# Power_Outlet.net
KiCad netlist of a schematic drawn in EAGLE
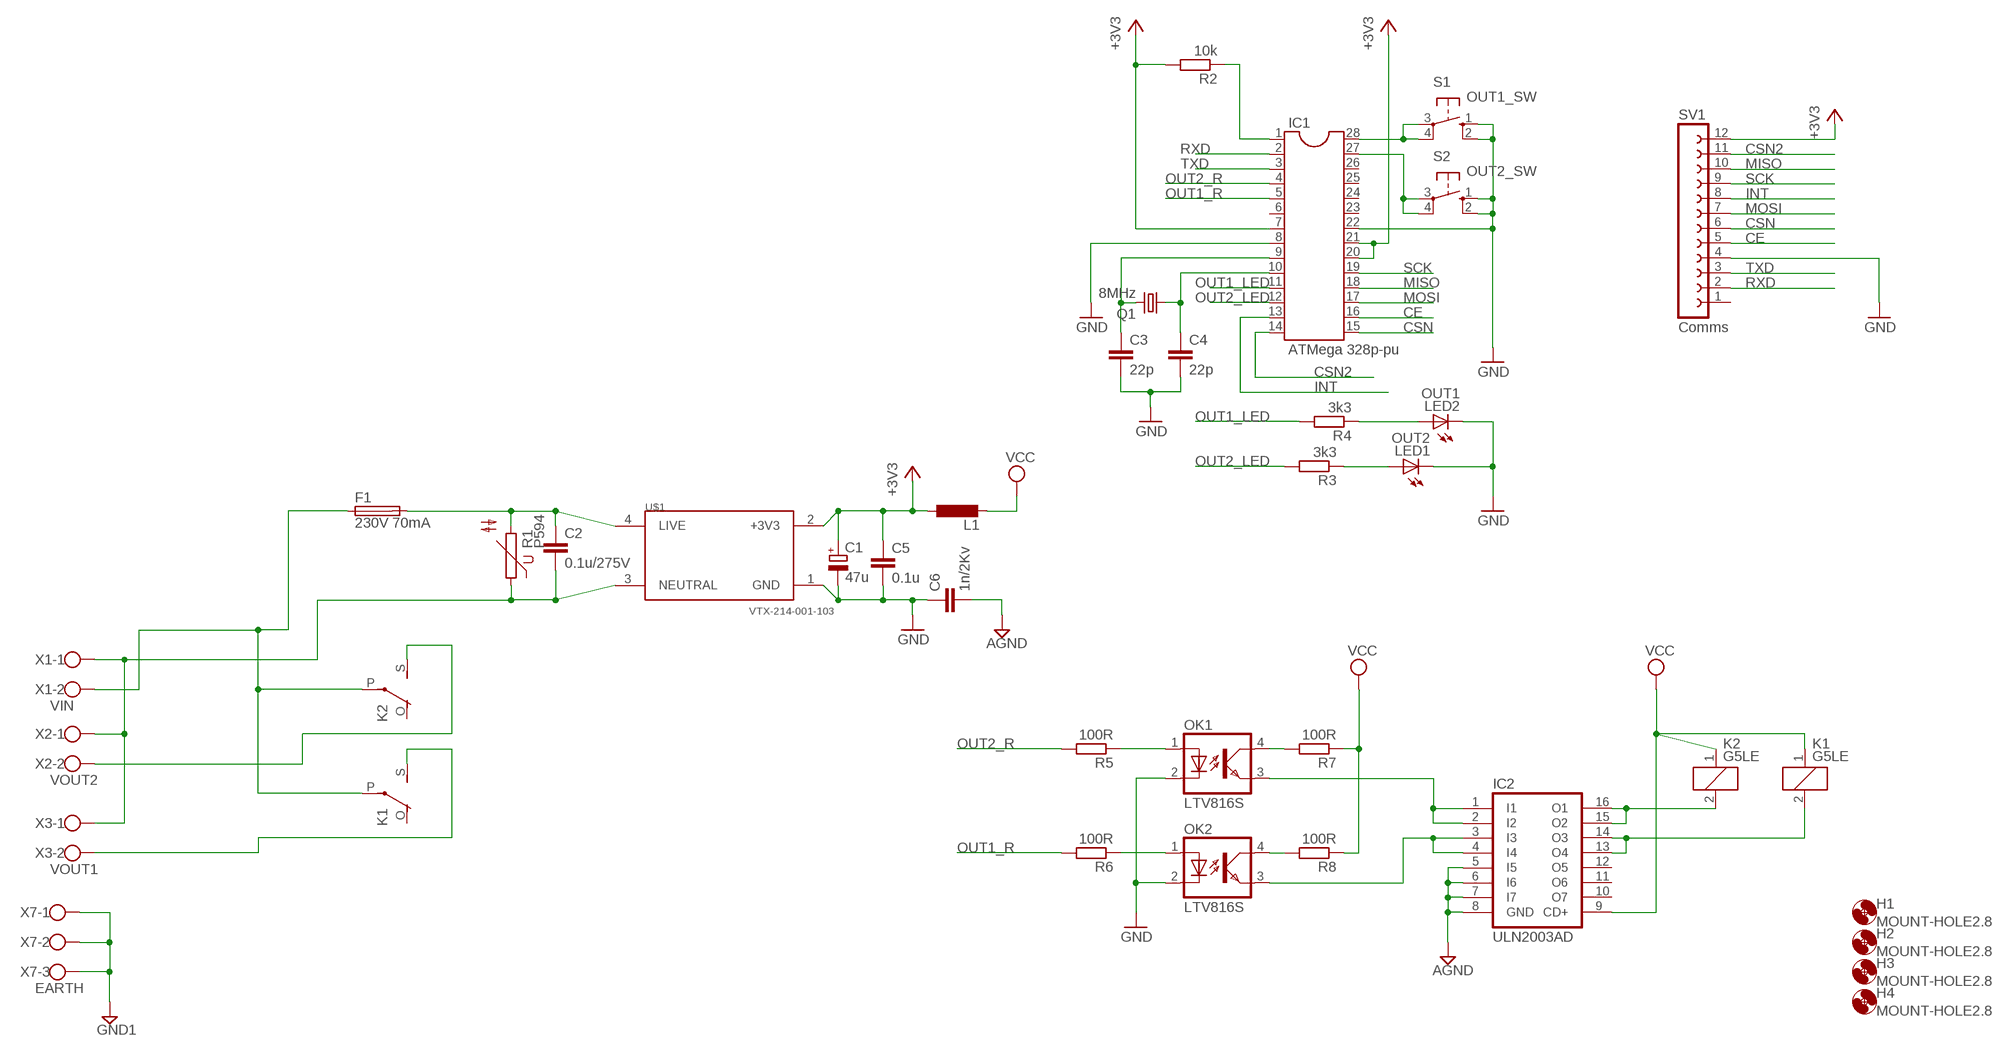
[diagram p0: schematic, sheet 1]

(export (version "E")
  (design (tool "Eeschema 10.0.6"))
  (components
    (comp (ref "C1")
      (value "47u")
      (footprint "eagle-import:E2,5-6E")
      (libsource (lib "eagle-import") (part "CPOL-EUE2,5-6E"))
    )
    (comp (ref "C2")
      (value "0.1u/275V")
      (footprint "eagle-import:C050-030X075")
      (libsource (lib "eagle-import") (part "C-EU050-030X075"))
    )
    (comp (ref "C3")
      (value "22p")
      (footprint "eagle-import:C1206K")
      (libsource (lib "eagle-import") (part "C-EUC1206K"))
    )
    (comp (ref "C4")
      (value "22p")
      (footprint "eagle-import:C1206K")
      (libsource (lib "eagle-import") (part "C-EUC1206K"))
    )
    (comp (ref "C5")
      (value "0.1u")
      (footprint "eagle-import:C1206K")
      (libsource (lib "eagle-import") (part "C-EUC1206K"))
    )
    (comp (ref "C6")
      (value "1n/2Kv")
      (footprint "eagle-import:C1206K")
      (libsource (lib "eagle-import") (part "C-EUC1206K"))
    )
    (comp (ref "F1")
      (value "230V 70mA")
      (footprint "eagle-import:SH22,5A")
      (libsource (lib "eagle-import") (part "FUSESH22,5A"))
    )
    (comp (ref "H1")
      (value "MOUNT-HOLE2.8")
      (footprint "eagle-import:2,8")
      (libsource (lib "eagle-import") (part "MOUNT-HOLE2.8"))
    )
    (comp (ref "H2")
      (value "MOUNT-HOLE2.8")
      (footprint "eagle-import:2,8")
      (libsource (lib "eagle-import") (part "MOUNT-HOLE2.8"))
    )
    (comp (ref "H3")
      (value "MOUNT-HOLE2.8")
      (footprint "eagle-import:2,8")
      (libsource (lib "eagle-import") (part "MOUNT-HOLE2.8"))
    )
    (comp (ref "H4")
      (value "MOUNT-HOLE2.8")
      (footprint "eagle-import:2,8")
      (libsource (lib "eagle-import") (part "MOUNT-HOLE2.8"))
    )
    (comp (ref "IC1")
      (value "ATMega 328p-pu")
      (footprint "eagle-import:DIL28-3")
      (libsource (lib "eagle-import") (part "DIL28-3"))
    )
    (comp (ref "IC2")
      (value "ULN2003AD")
      (footprint "eagle-import:SO16")
      (libsource (lib "eagle-import") (part "ULN2003AD"))
    )
    (comp (ref "K1")
      (value "G5LE")
      (footprint "eagle-import:G5LE")
      (libsource (lib "eagle-import") (part "G5LE"))
    )
    (comp (ref "K2")
      (value "G5LE")
      (footprint "eagle-import:G5LE")
      (libsource (lib "eagle-import") (part "G5LE"))
    )
    (comp (ref "L1")
      (value "L-EUL3225P")
      (footprint "eagle-import:L3225P")
      (libsource (lib "eagle-import") (part "L-EUL3225P"))
    )
    (comp (ref "LED1")
      (value "OUT2")
      (footprint "eagle-import:LED5MM")
      (libsource (lib "eagle-import") (part "LED5MM"))
    )
    (comp (ref "LED2")
      (value "OUT1")
      (footprint "eagle-import:LED5MM")
      (libsource (lib "eagle-import") (part "LED5MM"))
    )
    (comp (ref "OK1")
      (value "LTV816S")
      (footprint "eagle-import:SMD4")
      (libsource (lib "eagle-import") (part "LTV816S"))
    )
    (comp (ref "OK2")
      (value "LTV816S")
      (footprint "eagle-import:SMD4")
      (libsource (lib "eagle-import") (part "LTV816S"))
    )
    (comp (ref "Q1")
      (value "8MHz")
      (footprint "eagle-import:HC49_S")
      (libsource (lib "eagle-import") (part "CRYSTALHC49S"))
    )
    (comp (ref "R1")
      (value "P594")
      (footprint "eagle-import:P594")
      (libsource (lib "eagle-import") (part "P594"))
    )
    (comp (ref "R2")
      (value "10k")
      (footprint "eagle-import:R1206W")
      (libsource (lib "eagle-import") (part "R-EU_R1206W"))
    )
    (comp (ref "R3")
      (value "3k3")
      (footprint "eagle-import:R1206W")
      (libsource (lib "eagle-import") (part "R-EU_R1206W"))
    )
    (comp (ref "R4")
      (value "3k3")
      (footprint "eagle-import:R1206W")
      (libsource (lib "eagle-import") (part "R-EU_R1206W"))
    )
    (comp (ref "R5")
      (value "100R")
      (footprint "eagle-import:R1206W")
      (libsource (lib "eagle-import") (part "R-EU_R1206W"))
    )
    (comp (ref "R6")
      (value "100R")
      (footprint "eagle-import:R1206W")
      (libsource (lib "eagle-import") (part "R-EU_R1206W"))
    )
    (comp (ref "R7")
      (value "100R")
      (footprint "eagle-import:R1206W")
      (libsource (lib "eagle-import") (part "R-EU_R1206W"))
    )
    (comp (ref "R8")
      (value "100R")
      (footprint "eagle-import:R1206W")
      (libsource (lib "eagle-import") (part "R-EU_R1206W"))
    )
    (comp (ref "S1")
      (value "OUT1_SW")
      (footprint "eagle-import:B3F-40XX")
      (fields (field (name "MF") "OMRON COMPONENTS USA") (field (name "MPN") "B3F-4000"))
      (libsource (lib "eagle-import") (part "40-XX"))
    )
    (comp (ref "S2")
      (value "OUT2_SW")
      (footprint "eagle-import:B3F-40XX")
      (fields (field (name "MF") "OMRON COMPONENTS USA") (field (name "MPN") "B3F-4000"))
      (libsource (lib "eagle-import") (part "40-XX"))
    )
    (comp (ref "SV1")
      (value "Comms")
      (footprint "eagle-import:FE12W")
      (libsource (lib "eagle-import") (part "FE12W"))
    )
    (comp (ref "U$1")
      (value "VTX-214-001-103")
      (footprint "eagle-import:VTX214001103")
      (libsource (lib "eagle-import") (part "VTX-214-001-103"))
    )
    (comp (ref "X1")
      (value "VIN")
      (footprint "eagle-import:W237-102")
      (fields (field (name "MPN") "237-102"))
      (libsource (lib "eagle-import") (part "W237-102"))
    )
    (comp (ref "X2")
      (value "VOUT2")
      (footprint "eagle-import:W237-102")
      (fields (field (name "MPN") "237-102"))
      (libsource (lib "eagle-import") (part "W237-102"))
    )
    (comp (ref "X3")
      (value "VOUT1")
      (footprint "eagle-import:W237-102")
      (fields (field (name "MPN") "237-102"))
      (libsource (lib "eagle-import") (part "W237-102"))
    )
    (comp (ref "X7")
      (value "EARTH")
      (footprint "eagle-import:W237-103")
      (fields (field (name "MPN") "237-103"))
      (libsource (lib "eagle-import") (part "W237-103"))
    )
  )
  (nets
    (net (code "1") (name "+3V3") (class "Default")
      (node (ref "C1") (pin "+") (pinfunction "+_+") (pintype "passive"))
      (node (ref "C5") (pin "1") (pinfunction "1_1") (pintype "passive"))
      (node (ref "IC1") (pin "20") (pinfunction "20_20") (pintype "passive"))
      (node (ref "IC1") (pin "21") (pinfunction "21_21") (pintype "passive"))
      (node (ref "IC1") (pin "7") (pinfunction "7_7") (pintype "passive"))
      (node (ref "L1") (pin "1") (pinfunction "1_1") (pintype "passive"))
      (node (ref "R2") (pin "2") (pinfunction "2_2") (pintype "passive"))
      (node (ref "SV1") (pin "12") (pinfunction "12_12") (pintype "passive"))
      (node (ref "U$1") (pin "2") (pinfunction "+3V3_2") (pintype "power_in"))
    )
    (net (code "2") (name "/CE") (class "Default")
      (node (ref "IC1") (pin "16") (pinfunction "16_16") (pintype "passive"))
      (node (ref "SV1") (pin "5") (pinfunction "5_5") (pintype "passive"))
    )
    (net (code "3") (name "/CSN") (class "Default")
      (node (ref "IC1") (pin "15") (pinfunction "15_15") (pintype "passive"))
      (node (ref "SV1") (pin "6") (pinfunction "6_6") (pintype "passive"))
    )
    (net (code "4") (name "/CSN2") (class "Default")
      (node (ref "IC1") (pin "14") (pinfunction "14_14") (pintype "passive"))
      (node (ref "SV1") (pin "11") (pinfunction "11_11") (pintype "passive"))
    )
    (net (code "5") (name "/INT") (class "Default")
      (node (ref "IC1") (pin "13") (pinfunction "13_13") (pintype "passive"))
      (node (ref "SV1") (pin "8") (pinfunction "8_8") (pintype "passive"))
    )
    (net (code "6") (name "/MISO") (class "Default")
      (node (ref "IC1") (pin "18") (pinfunction "18_18") (pintype "passive"))
      (node (ref "SV1") (pin "10") (pinfunction "10_10") (pintype "passive"))
    )
    (net (code "7") (name "/MOSI") (class "Default")
      (node (ref "IC1") (pin "17") (pinfunction "17_17") (pintype "passive"))
      (node (ref "SV1") (pin "7") (pinfunction "7_7") (pintype "passive"))
    )
    (net (code "8") (name "/OUT1_LED") (class "Default")
      (node (ref "IC1") (pin "11") (pinfunction "11_11") (pintype "passive"))
      (node (ref "R4") (pin "2") (pinfunction "2_2") (pintype "passive"))
    )
    (net (code "9") (name "/OUT1_R") (class "Default")
      (node (ref "IC1") (pin "5") (pinfunction "5_5") (pintype "passive"))
      (node (ref "R6") (pin "2") (pinfunction "2_2") (pintype "passive"))
    )
    (net (code "10") (name "/OUT2_LED") (class "Default")
      (node (ref "IC1") (pin "12") (pinfunction "12_12") (pintype "passive"))
      (node (ref "R3") (pin "2") (pinfunction "2_2") (pintype "passive"))
    )
    (net (code "11") (name "/OUT2_R") (class "Default")
      (node (ref "IC1") (pin "4") (pinfunction "4_4") (pintype "passive"))
      (node (ref "R5") (pin "2") (pinfunction "2_2") (pintype "passive"))
    )
    (net (code "12") (name "/RXD") (class "Default")
      (node (ref "IC1") (pin "2") (pinfunction "2_2") (pintype "passive"))
      (node (ref "SV1") (pin "2") (pinfunction "2_2") (pintype "passive"))
    )
    (net (code "13") (name "/SCK") (class "Default")
      (node (ref "IC1") (pin "19") (pinfunction "19_19") (pintype "passive"))
      (node (ref "SV1") (pin "9") (pinfunction "9_9") (pintype "passive"))
    )
    (net (code "14") (name "/TXD") (class "Default")
      (node (ref "IC1") (pin "3") (pinfunction "3_3") (pintype "passive"))
      (node (ref "SV1") (pin "3") (pinfunction "3_3") (pintype "passive"))
    )
    (net (code "15") (name "AGND") (class "Default")
      (node (ref "C6") (pin "2") (pinfunction "2_2") (pintype "passive"))
      (node (ref "IC2") (pin "5") (pinfunction "I5_5") (pintype "input"))
      (node (ref "IC2") (pin "6") (pinfunction "I6_6") (pintype "input"))
      (node (ref "IC2") (pin "7") (pinfunction "I7_7") (pintype "input"))
      (node (ref "IC2") (pin "8") (pinfunction "GND_8") (pintype "power_in"))
    )
    (net (code "16") (name "GND") (class "Default")
      (node (ref "C1") (pin "-") (pinfunction "-_-") (pintype "passive"))
      (node (ref "C3") (pin "2") (pinfunction "2_2") (pintype "passive"))
      (node (ref "C4") (pin "2") (pinfunction "2_2") (pintype "passive"))
      (node (ref "C5") (pin "2") (pinfunction "2_2") (pintype "passive"))
      (node (ref "C6") (pin "1") (pinfunction "1_1") (pintype "passive"))
      (node (ref "IC1") (pin "22") (pinfunction "22_22") (pintype "passive"))
      (node (ref "IC1") (pin "8") (pinfunction "8_8") (pintype "passive"))
      (node (ref "LED1") (pin "K") (pinfunction "C_K") (pintype "passive"))
      (node (ref "LED2") (pin "K") (pinfunction "C_K") (pintype "passive"))
      (node (ref "OK1") (pin "2") (pinfunction "C_2") (pintype "passive"))
      (node (ref "OK2") (pin "2") (pinfunction "C_2") (pintype "passive"))
      (node (ref "S1") (pin "1") (pinfunction "S_1") (pintype "passive"))
      (node (ref "S1") (pin "2") (pinfunction "S1_2") (pintype "passive"))
      (node (ref "S2") (pin "1") (pinfunction "S_1") (pintype "passive"))
      (node (ref "S2") (pin "2") (pinfunction "S1_2") (pintype "passive"))
      (node (ref "SV1") (pin "4") (pinfunction "4_4") (pintype "passive"))
      (node (ref "U$1") (pin "1") (pinfunction "GND_1") (pintype "power_in"))
    )
    (net (code "17") (name "GND1") (class "Default")
      (node (ref "X7") (pin "1") (pinfunction "KL_1") (pintype "passive"))
      (node (ref "X7") (pin "2") (pinfunction "KL_2") (pintype "passive"))
      (node (ref "X7") (pin "3") (pinfunction "KL_3") (pintype "passive"))
    )
    (net (code "18") (name "Net-(C3-Pad1)") (class "Default")
      (node (ref "C3") (pin "1") (pinfunction "1_1") (pintype "passive"))
      (node (ref "IC1") (pin "9") (pinfunction "9_9") (pintype "passive"))
      (node (ref "Q1") (pin "2") (pinfunction "2_2") (pintype "passive"))
    )
    (net (code "19") (name "Net-(C4-Pad1)") (class "Default")
      (node (ref "C4") (pin "1") (pinfunction "1_1") (pintype "passive"))
      (node (ref "IC1") (pin "10") (pinfunction "10_10") (pintype "passive"))
      (node (ref "Q1") (pin "1") (pinfunction "1_1") (pintype "passive"))
    )
    (net (code "20") (name "Net-(IC1-Pad1)") (class "Default")
      (node (ref "IC1") (pin "1") (pinfunction "1_1") (pintype "passive"))
      (node (ref "R2") (pin "1") (pinfunction "1_1") (pintype "passive"))
    )
    (net (code "21") (name "Net-(IC2-I1)") (class "Default")
      (node (ref "IC2") (pin "1") (pinfunction "I1_1") (pintype "input"))
      (node (ref "IC2") (pin "2") (pinfunction "I2_2") (pintype "input"))
      (node (ref "OK1") (pin "3") (pinfunction "EMIT_3") (pintype "passive"))
    )
    (net (code "22") (name "Net-(IC2-I3)") (class "Default")
      (node (ref "IC2") (pin "3") (pinfunction "I3_3") (pintype "input"))
      (node (ref "IC2") (pin "4") (pinfunction "I4_4") (pintype "input"))
      (node (ref "OK2") (pin "3") (pinfunction "EMIT_3") (pintype "passive"))
    )
    (net (code "23") (name "Net-(IC2-O1)") (class "Default")
      (node (ref "IC2") (pin "15") (pinfunction "O2_15") (pintype "open_collector"))
      (node (ref "IC2") (pin "16") (pinfunction "O1_16") (pintype "open_collector"))
      (node (ref "K2") (pin "2") (pinfunction "2_2") (pintype "passive"))
    )
    (net (code "24") (name "Net-(IC2-O3)") (class "Default")
      (node (ref "IC2") (pin "13") (pinfunction "O4_13") (pintype "open_collector"))
      (node (ref "IC2") (pin "14") (pinfunction "O3_14") (pintype "open_collector"))
      (node (ref "K1") (pin "2") (pinfunction "2_2") (pintype "passive"))
    )
    (net (code "25") (name "Net-(LED1-PadA)") (class "Default")
      (node (ref "LED1") (pin "A") (pinfunction "A_A") (pintype "passive"))
      (node (ref "R3") (pin "1") (pinfunction "1_1") (pintype "passive"))
    )
    (net (code "26") (name "Net-(LED2-PadA)") (class "Default")
      (node (ref "LED2") (pin "A") (pinfunction "A_A") (pintype "passive"))
      (node (ref "R4") (pin "1") (pinfunction "1_1") (pintype "passive"))
    )
    (net (code "27") (name "Net-(OK1-A)") (class "Default")
      (node (ref "OK1") (pin "1") (pinfunction "A_1") (pintype "passive"))
      (node (ref "R5") (pin "1") (pinfunction "1_1") (pintype "passive"))
    )
    (net (code "28") (name "Net-(OK1-COL)") (class "Default")
      (node (ref "OK1") (pin "4") (pinfunction "COL_4") (pintype "passive"))
      (node (ref "R7") (pin "2") (pinfunction "2_2") (pintype "passive"))
    )
    (net (code "29") (name "Net-(OK2-A)") (class "Default")
      (node (ref "OK2") (pin "1") (pinfunction "A_1") (pintype "passive"))
      (node (ref "R6") (pin "1") (pinfunction "1_1") (pintype "passive"))
    )
    (net (code "30") (name "Net-(OK2-COL)") (class "Default")
      (node (ref "OK2") (pin "4") (pinfunction "COL_4") (pintype "passive"))
      (node (ref "R8") (pin "2") (pinfunction "2_2") (pintype "passive"))
    )
    (net (code "31") (name "Net-(S1-P)") (class "Default")
      (node (ref "IC1") (pin "28") (pinfunction "28_28") (pintype "passive"))
      (node (ref "S1") (pin "3") (pinfunction "P_3") (pintype "passive"))
      (node (ref "S1") (pin "4") (pinfunction "P1_4") (pintype "passive"))
    )
    (net (code "32") (name "Net-(S2-P)") (class "Default")
      (node (ref "IC1") (pin "27") (pinfunction "27_27") (pintype "passive"))
      (node (ref "S2") (pin "3") (pinfunction "P_3") (pintype "passive"))
      (node (ref "S2") (pin "4") (pinfunction "P1_4") (pintype "passive"))
    )
    (net (code "33") (name "Net-(U$1-LIVE)") (class "Default")
      (node (ref "C2") (pin "1") (pinfunction "1_1") (pintype "passive"))
      (node (ref "F1") (pin "2") (pinfunction "2_2") (pintype "passive"))
      (node (ref "R1") (pin "2") (pinfunction "2_2") (pintype "passive"))
      (node (ref "U$1") (pin "4") (pinfunction "LIVE_4") (pintype "input"))
    )
    (net (code "34") (name "Net-(U$1-NEUTRAL)") (class "Default")
      (node (ref "C2") (pin "2") (pinfunction "2_2") (pintype "passive"))
      (node (ref "R1") (pin "1") (pinfunction "1_1") (pintype "passive"))
      (node (ref "U$1") (pin "3") (pinfunction "NEUTRAL_3") (pintype "input"))
      (node (ref "X1") (pin "1") (pinfunction "KL_1") (pintype "passive"))
      (node (ref "X2") (pin "1") (pinfunction "KL_1") (pintype "passive"))
      (node (ref "X3") (pin "1") (pinfunction "KL_1") (pintype "passive"))
    )
    (net (code "35") (name "Net-(X1B-KL)") (class "Default")
      (node (ref "F1") (pin "1") (pinfunction "1_1") (pintype "passive"))
      (node (ref "K1") (pin "P") (pinfunction "P_P") (pintype "passive"))
      (node (ref "K2") (pin "P") (pinfunction "P_P") (pintype "passive"))
      (node (ref "X1") (pin "2") (pinfunction "KL_2") (pintype "passive"))
    )
    (net (code "36") (name "Net-(X2B-KL)") (class "Default")
      (node (ref "K2") (pin "S") (pinfunction "S_S") (pintype "passive"))
      (node (ref "X2") (pin "2") (pinfunction "KL_2") (pintype "passive"))
    )
    (net (code "37") (name "Net-(X3B-KL)") (class "Default")
      (node (ref "K1") (pin "S") (pinfunction "S_S") (pintype "passive"))
      (node (ref "X3") (pin "2") (pinfunction "KL_2") (pintype "passive"))
    )
    (net (code "38") (name "VCC") (class "Default")
      (node (ref "IC2") (pin "9") (pinfunction "CD+_9") (pintype "passive"))
      (node (ref "K1") (pin "1") (pinfunction "1_1") (pintype "passive"))
      (node (ref "K2") (pin "1") (pinfunction "1_1") (pintype "passive"))
      (node (ref "L1") (pin "2") (pinfunction "2_2") (pintype "passive"))
      (node (ref "R7") (pin "1") (pinfunction "1_1") (pintype "passive"))
      (node (ref "R8") (pin "1") (pinfunction "1_1") (pintype "passive"))
    )
    (net (code "39") (name "unconnected-(IC1-Pad6)") (class "Default")
      (node (ref "IC1") (pin "6") (pinfunction "6_6") (pintype "passive"))
    )
    (net (code "40") (name "unconnected-(IC1-Pad23)") (class "Default")
      (node (ref "IC1") (pin "23") (pinfunction "23_23") (pintype "passive"))
    )
    (net (code "41") (name "unconnected-(IC1-Pad24)") (class "Default")
      (node (ref "IC1") (pin "24") (pinfunction "24_24") (pintype "passive"))
    )
    (net (code "42") (name "unconnected-(IC1-Pad25)") (class "Default")
      (node (ref "IC1") (pin "25") (pinfunction "25_25") (pintype "passive"))
    )
    (net (code "43") (name "unconnected-(IC1-Pad26)") (class "Default")
      (node (ref "IC1") (pin "26") (pinfunction "26_26") (pintype "passive"))
    )
    (net (code "44") (name "unconnected-(IC2-O5-Pad12)") (class "Default")
      (node (ref "IC2") (pin "12") (pinfunction "O5_12") (pintype "open_collector"))
    )
    (net (code "45") (name "unconnected-(IC2-O6-Pad11)") (class "Default")
      (node (ref "IC2") (pin "11") (pinfunction "O6_11") (pintype "open_collector"))
    )
    (net (code "46") (name "unconnected-(IC2-O7-Pad10)") (class "Default")
      (node (ref "IC2") (pin "10") (pinfunction "O7_10") (pintype "open_collector"))
    )
    (net (code "47") (name "unconnected-(K1-PadO)") (class "Default")
      (node (ref "K1") (pin "O") (pinfunction "O_O") (pintype "passive"))
    )
    (net (code "48") (name "unconnected-(K2-PadO)") (class "Default")
      (node (ref "K2") (pin "O") (pinfunction "O_O") (pintype "passive"))
    )
    (net (code "49") (name "unconnected-(SV1-Pad1)") (class "Default")
      (node (ref "SV1") (pin "1") (pinfunction "1_1") (pintype "passive"))
    )
  )
)
